# 5.net
KiCad netlist of a schematic drawn in Altium Designer
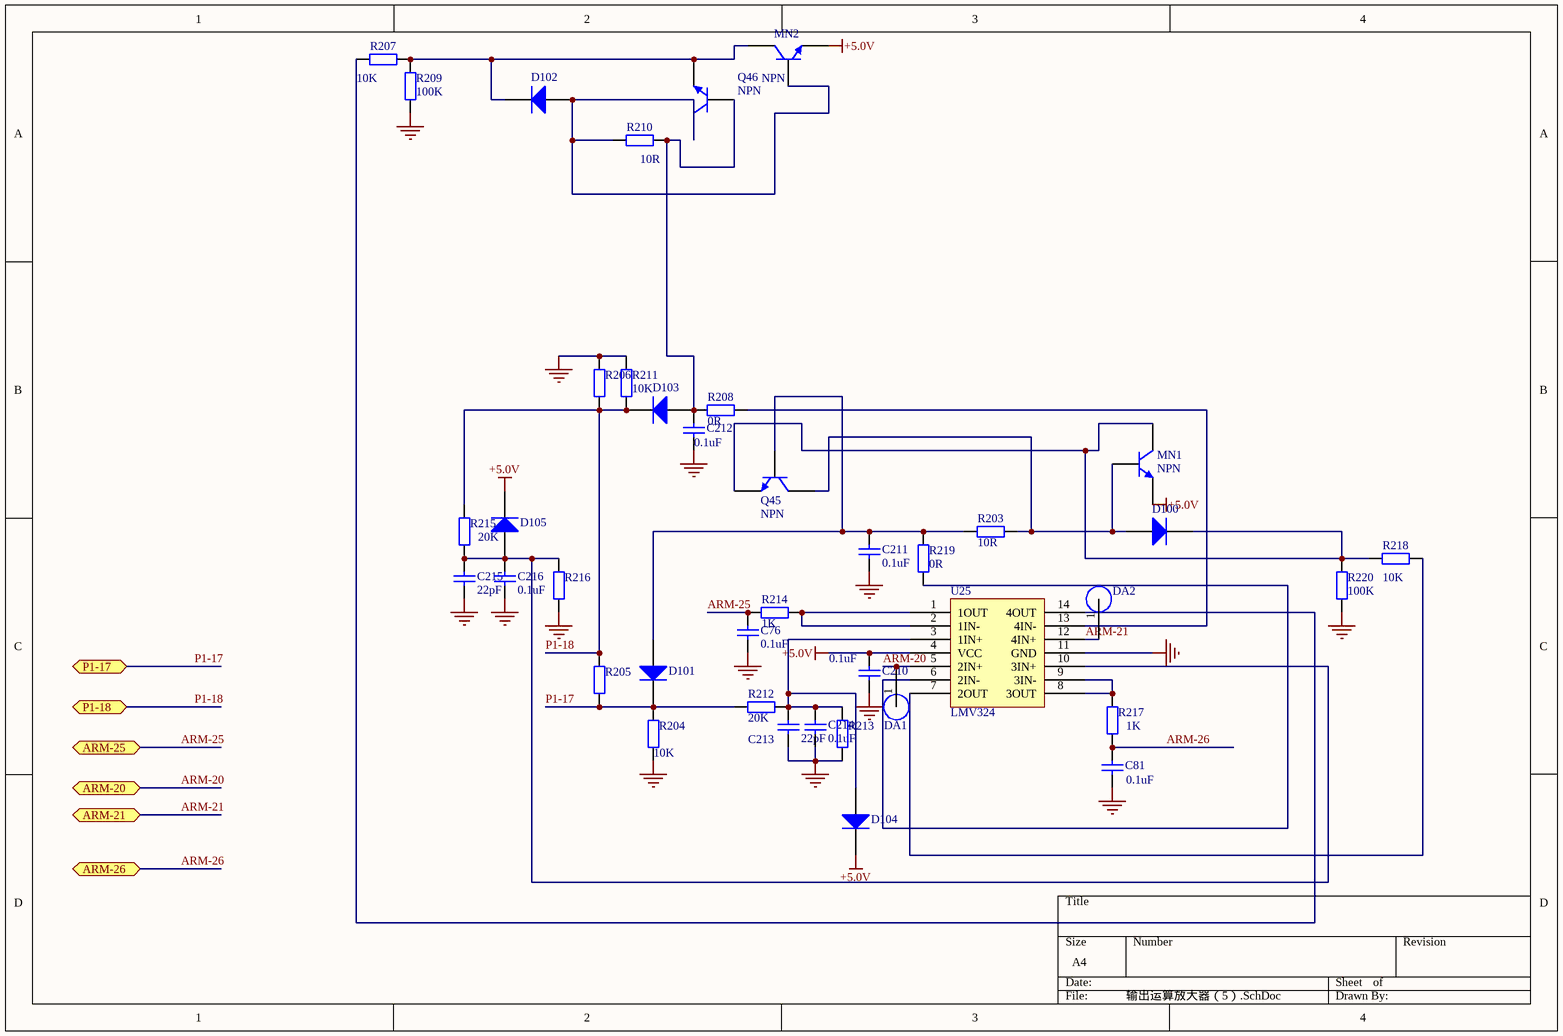
[diagram p0: 输出运算放大器（5）.SchDoc]

(export (version "E")
  (design (tool "Eeschema 10.0.6"))
  (components
    (comp (ref "C76")
      (value "0.1uF")
      (footprint "采集板3.0增加1路模拟量2:C0805")
      (description "Capacitor")
      (fields (field (name "Comment") "Cap") (field (name "PUBLISHER") "Altium Limited"))
      (libsource (lib "Miscellaneous Devices") (part "Cap"))
    )
    (comp (ref "C81")
      (value "0.1uF")
      (footprint "采集板3.0增加1路模拟量2:C0805")
      (description "Capacitor")
      (fields (field (name "Comment") "Cap") (field (name "PUBLISHER") "Altium Limited"))
      (libsource (lib "Miscellaneous Devices") (part "Cap"))
    )
    (comp (ref "C210")
      (value "0.1uF")
      (footprint "采集板3.0增加1路模拟量2:C0805")
      (description "Capacitor")
      (fields (field (name "Comment") "Cap") (field (name "PUBLISHER") "Altium Limited"))
      (libsource (lib "Miscellaneous Devices") (part "Cap"))
    )
    (comp (ref "C211")
      (value "0.1uF")
      (footprint "采集板3.0增加1路模拟量2:C0805")
      (description "Capacitor")
      (fields (field (name "Comment") "Cap") (field (name "PUBLISHER") "Altium Limited"))
      (libsource (lib "Miscellaneous Devices") (part "Cap"))
    )
    (comp (ref "C212")
      (value "0.1uF")
      (footprint "采集板3.0增加1路模拟量2:C0805")
      (description "Capacitor")
      (fields (field (name "Comment") "Cap") (field (name "PUBLISHER") "Altium Limited"))
      (libsource (lib "Miscellaneous Devices") (part "Cap"))
    )
    (comp (ref "C213")
      (value "22pF")
      (footprint "采集板3.0增加1路模拟量2:C0805")
      (description "Capacitor")
      (fields (field (name "Comment") "Cap") (field (name "PUBLISHER") "Altium Limited"))
      (libsource (lib "Miscellaneous Devices") (part "Cap"))
    )
    (comp (ref "C214")
      (value "0.1uF")
      (footprint "采集板3.0增加1路模拟量2:C0805")
      (description "Capacitor")
      (fields (field (name "Comment") "Cap") (field (name "PUBLISHER") "Altium Limited"))
      (libsource (lib "Miscellaneous Devices") (part "Cap"))
    )
    (comp (ref "C215")
      (value "22pF")
      (footprint "采集板3.0增加1路模拟量2:C0805")
      (description "Capacitor")
      (fields (field (name "Comment") "Cap") (field (name "PUBLISHER") "Altium Limited"))
      (libsource (lib "Miscellaneous Devices") (part "Cap"))
    )
    (comp (ref "C216")
      (value "0.1uF")
      (footprint "采集板3.0增加1路模拟量2:C0805")
      (description "Capacitor")
      (fields (field (name "Comment") "Cap") (field (name "PUBLISHER") "Altium Limited"))
      (libsource (lib "Miscellaneous Devices") (part "Cap"))
    )
    (comp (ref "D100")
      (value "Diode 1N4007")
      (footprint "SOD123")
      (description "1 Amp General Purpose Rectifier")
      (fields (field (name "PUBLISHER") "Altium Limited"))
      (libsource (lib "Miscellaneous Devices") (part "Diode 1N4007"))
    )
    (comp (ref "D101")
      (value "Diode 1N4007")
      (footprint "SMA")
      (description "1 Amp General Purpose Rectifier")
      (fields (field (name "PUBLISHER") "Altium Limited"))
      (libsource (lib "Miscellaneous Devices") (part "Diode 1N4007"))
    )
    (comp (ref "D102")
      (value "Diode 1N4007")
      (footprint "SOD123")
      (description "1 Amp General Purpose Rectifier")
      (fields (field (name "PUBLISHER") "Altium Limited"))
      (libsource (lib "Miscellaneous Devices") (part "Diode 1N4007"))
    )
    (comp (ref "D103")
      (value "Diode 1N4007")
      (footprint "SMA")
      (description "1 Amp General Purpose Rectifier")
      (fields (field (name "PUBLISHER") "Altium Limited"))
      (libsource (lib "Miscellaneous Devices") (part "Diode 1N4007"))
    )
    (comp (ref "D104")
      (value "Diode 1N4007")
      (footprint "SOD123")
      (description "1 Amp General Purpose Rectifier")
      (fields (field (name "PUBLISHER") "Altium Limited"))
      (libsource (lib "Miscellaneous Devices") (part "Diode 1N4007"))
    )
    (comp (ref "D105")
      (value "Diode 1N4007")
      (footprint "SOD123")
      (description "1 Amp General Purpose Rectifier")
      (fields (field (name "PUBLISHER") "Altium Limited"))
      (libsource (lib "Miscellaneous Devices") (part "Diode 1N4007"))
    )
    (comp (ref "DA1") (value "PIN") (footprint "圆形焊盘") (libsource (lib "圆孔") (part "Component_1")))
    (comp (ref "DA2") (value "PIN") (footprint "圆形焊盘") (libsource (lib "圆孔") (part "Component_1")))
    (comp (ref "MN1")
      (value "NPN")
      (footprint "SOT23-3")
      (description "NPN Bipolar Transistor")
      (fields (field (name "PUBLISHER") "Altium Limited"))
      (libsource (lib "Miscellaneous Devices") (part "NPN"))
    )
    (comp (ref "MN2")
      (value "NPN")
      (footprint "MN2")
      (description "NPN Bipolar Transistor")
      (fields (field (name "PUBLISHER") "Altium Limited"))
      (libsource (lib "Miscellaneous Devices") (part "NPN"))
    )
    (comp (ref "Q45")
      (value "NPN")
      (footprint "Q45")
      (description "NPN Bipolar Transistor")
      (fields (field (name "PUBLISHER") "Altium Limited"))
      (libsource (lib "Miscellaneous Devices") (part "NPN"))
    )
    (comp (ref "Q46")
      (value "NPN")
      (footprint "Q46")
      (description "NPN Bipolar Transistor")
      (fields (field (name "PUBLISHER") "Altium Limited"))
      (libsource (lib "Miscellaneous Devices") (part "NPN"))
    )
    (comp (ref "R203")
      (value "10R")
      (footprint "R1206")
      (description "Resistor")
      (fields (field (name "Comment") "Res2") (field (name "PUBLISHER") "Altium Limited"))
      (libsource (lib "") (part "Res2_1"))
    )
    (comp (ref "R204")
      (value "10K")
      (footprint "采集板3.0增加1路模拟量2:R0805")
      (description "Resistor")
      (fields (field (name "Comment") "Res2") (field (name "PUBLISHER") "Altium Limited"))
      (libsource (lib "") (part "Res2_3"))
    )
    (comp (ref "R205")
      (value "Res2")
      (footprint "R1206")
      (description "Resistor")
      (fields (field (name "PUBLISHER") "Altium Limited"))
      (libsource (lib "") (part "Res2_2"))
    )
    (comp (ref "R206")
      (value "Res2")
      (footprint "R1206")
      (description "Resistor")
      (fields (field (name "PUBLISHER") "Altium Limited"))
      (libsource (lib "") (part "Res2_2"))
    )
    (comp (ref "R207")
      (value "10K")
      (footprint "采集板3.0增加1路模拟量2:R0805")
      (description "Resistor")
      (fields (field (name "Comment") "Res2") (field (name "PUBLISHER") "Altium Limited"))
      (libsource (lib "") (part "Res2_1"))
    )
    (comp (ref "R208")
      (value "0R")
      (footprint "采集板3.0增加1路模拟量2:R0805")
      (description "Resistor")
      (fields (field (name "Comment") "Res2") (field (name "PUBLISHER") "Altium Limited"))
      (libsource (lib "Miscellaneous Devices") (part "Res2"))
    )
    (comp (ref "R209")
      (value "100K")
      (footprint "采集板3.0增加1路模拟量2:R0805")
      (description "Resistor")
      (fields (field (name "Comment") "Res2") (field (name "PUBLISHER") "Altium Limited"))
      (libsource (lib "") (part "Res2_3"))
    )
    (comp (ref "R210")
      (value "10R")
      (footprint "R1206")
      (description "Resistor")
      (fields (field (name "Comment") "Res2") (field (name "PUBLISHER") "Altium Limited"))
      (libsource (lib "") (part "Res2_1"))
    )
    (comp (ref "R211")
      (value "10K")
      (footprint "采集板3.0增加1路模拟量2:R0805")
      (description "Resistor")
      (fields (field (name "Comment") "Res2") (field (name "PUBLISHER") "Altium Limited"))
      (libsource (lib "") (part "Res2_2"))
    )
    (comp (ref "R212")
      (value "20K")
      (footprint "采集板3.0增加1路模拟量2:R0805")
      (description "Resistor")
      (fields (field (name "Comment") "Res2") (field (name "PUBLISHER") "Altium Limited"))
      (libsource (lib "") (part "Res2_1"))
    )
    (comp (ref "R213")
      (value "Res2")
      (footprint "R0805")
      (description "Resistor")
      (fields (field (name "PUBLISHER") "Altium Limited"))
      (libsource (lib "") (part "Res2_2"))
    )
    (comp (ref "R214")
      (value "1K")
      (footprint "采集板3.0增加1路模拟量2:R0805")
      (description "Resistor")
      (fields (field (name "Comment") "Res2") (field (name "PUBLISHER") "Altium Limited"))
      (libsource (lib "") (part "Res2_1"))
    )
    (comp (ref "R215")
      (value "20K")
      (footprint "采集板3.0增加1路模拟量2:R0805")
      (description "Resistor")
      (fields (field (name "Comment") "Res2") (field (name "PUBLISHER") "Altium Limited"))
      (libsource (lib "") (part "Res2_3"))
    )
    (comp (ref "R216")
      (value "Res2")
      (footprint "R0805")
      (description "Resistor")
      (fields (field (name "PUBLISHER") "Altium Limited"))
      (libsource (lib "") (part "Res2_2"))
    )
    (comp (ref "R217")
      (value "1K")
      (footprint "采集板3.0增加1路模拟量2:R0805")
      (description "Resistor")
      (fields (field (name "Comment") "Res2") (field (name "PUBLISHER") "Altium Limited"))
      (libsource (lib "") (part "Res2_2"))
    )
    (comp (ref "R218")
      (value "10K")
      (footprint "采集板3.0增加1路模拟量2:R0805")
      (description "Resistor")
      (fields (field (name "Comment") "Res2") (field (name "PUBLISHER") "Altium Limited"))
      (libsource (lib "Miscellaneous Devices") (part "Res2"))
    )
    (comp (ref "R219")
      (value "0R")
      (footprint "采集板3.0增加1路模拟量2:R0805")
      (description "Resistor")
      (fields (field (name "Comment") "Res2") (field (name "PUBLISHER") "Altium Limited"))
      (libsource (lib "") (part "Res2_2"))
    )
    (comp (ref "R220")
      (value "100K")
      (footprint "采集板3.0增加1路模拟量2:R0805")
      (description "Resistor")
      (fields (field (name "Comment") "Res2") (field (name "PUBLISHER") "Altium Limited"))
      (libsource (lib "") (part "Res2_2"))
    )
    (comp (ref "U25") (value "LMV324") (footprint "SOP-14") (libsource (lib "LMV324") (part "Component_1")))
  )
  (nets
    (net (code "1") (name "+5.0V") (class "Default")
      (node (ref "C210") (pin "1") (pinfunction "1_1") (pintype "passive"))
      (node (ref "D104") (pin "2") (pinfunction "K_2") (pintype "passive"))
      (node (ref "D105") (pin "2") (pinfunction "K_2") (pintype "passive"))
      (node (ref "MN1") (pin "3") (pinfunction "E_3") (pintype "passive"))
      (node (ref "MN2") (pin "3") (pinfunction "E_3") (pintype "passive"))
      (node (ref "U25") (pin "4") (pinfunction "VCC_4") (pintype "passive"))
    )
    (net (code "2") (name "/ARM-20") (class "Default")
      (node (ref "DA1") (pin "1") (pinfunction "1_1") (pintype "passive"))
      (node (ref "U25") (pin "5") (pinfunction "2IN+_5") (pintype "passive"))
    )
    (net (code "3") (name "/ARM-21") (class "Default")
      (node (ref "DA2") (pin "1") (pinfunction "1_1") (pintype "passive"))
      (node (ref "U25") (pin "12") (pinfunction "4IN+_12") (pintype "passive"))
    )
    (net (code "4") (name "/ARM-25") (class "Default")
      (node (ref "C76") (pin "2") (pinfunction "2_2") (pintype "passive"))
      (node (ref "R214") (pin "1") (pinfunction "1_1") (pintype "passive"))
    )
    (net (code "5") (name "/ARM-26") (class "Default")
      (node (ref "C81") (pin "2") (pinfunction "2_2") (pintype "passive"))
      (node (ref "R217") (pin "1") (pinfunction "1_1") (pintype "passive"))
    )
    (net (code "6") (name "/P1-17") (class "Default")
      (node (ref "D101") (pin "2") (pinfunction "K_2") (pintype "passive"))
      (node (ref "R204") (pin "1") (pinfunction "1_1") (pintype "passive"))
      (node (ref "R205") (pin "1") (pinfunction "1_1") (pintype "passive"))
      (node (ref "R212") (pin "1") (pinfunction "1_1") (pintype "passive"))
    )
    (net (code "7") (name "/P1-18") (class "Default")
      (node (ref "D103") (pin "2") (pinfunction "K_2") (pintype "passive"))
      (node (ref "R205") (pin "2") (pinfunction "2_2") (pintype "passive"))
      (node (ref "R206") (pin "1") (pinfunction "1_1") (pintype "passive"))
      (node (ref "R211") (pin "1") (pinfunction "1_1") (pintype "passive"))
      (node (ref "R215") (pin "1") (pinfunction "1_1") (pintype "passive"))
    )
    (net (code "8") (name "GND") (class "Default")
      (node (ref "C210") (pin "2") (pinfunction "2_2") (pintype "passive"))
      (node (ref "C211") (pin "2") (pinfunction "2_2") (pintype "passive"))
      (node (ref "C212") (pin "2") (pinfunction "2_2") (pintype "passive"))
      (node (ref "C213") (pin "1") (pinfunction "1_1") (pintype "passive"))
      (node (ref "C214") (pin "1") (pinfunction "1_1") (pintype "passive"))
      (node (ref "C215") (pin "1") (pinfunction "1_1") (pintype "passive"))
      (node (ref "C216") (pin "1") (pinfunction "1_1") (pintype "passive"))
      (node (ref "C76") (pin "1") (pinfunction "1_1") (pintype "passive"))
      (node (ref "C81") (pin "1") (pinfunction "1_1") (pintype "passive"))
      (node (ref "R204") (pin "2") (pinfunction "2_2") (pintype "passive"))
      (node (ref "R206") (pin "2") (pinfunction "2_2") (pintype "passive"))
      (node (ref "R209") (pin "2") (pinfunction "2_2") (pintype "passive"))
      (node (ref "R211") (pin "2") (pinfunction "2_2") (pintype "passive"))
      (node (ref "R213") (pin "1") (pinfunction "1_1") (pintype "passive"))
      (node (ref "R216") (pin "1") (pinfunction "1_1") (pintype "passive"))
      (node (ref "R220") (pin "1") (pinfunction "1_1") (pintype "passive"))
      (node (ref "U25") (pin "11") (pinfunction "GND_11") (pintype "passive"))
    )
    (net (code "9") (name "Net-(D100-A)") (class "Default")
      (node (ref "D100") (pin "1") (pinfunction "A_1") (pintype "passive"))
      (node (ref "MN1") (pin "2") (pinfunction "B_2") (pintype "passive"))
      (node (ref "Q45") (pin "1") (pinfunction "C_1") (pintype "passive"))
      (node (ref "R203") (pin "2") (pinfunction "2_2") (pintype "passive"))
    )
    (net (code "10") (name "Net-(D100-K)") (class "Default")
      (node (ref "D100") (pin "2") (pinfunction "K_2") (pintype "passive"))
      (node (ref "MN1") (pin "1") (pinfunction "C_1") (pintype "passive"))
      (node (ref "Q45") (pin "3") (pinfunction "E_3") (pintype "passive"))
      (node (ref "R218") (pin "2") (pinfunction "2_2") (pintype "passive"))
      (node (ref "R220") (pin "2") (pinfunction "2_2") (pintype "passive"))
    )
    (net (code "11") (name "Net-(D101-A)") (class "Default")
      (node (ref "C211") (pin "1") (pinfunction "1_1") (pintype "passive"))
      (node (ref "D101") (pin "1") (pinfunction "A_1") (pintype "passive"))
      (node (ref "Q45") (pin "2") (pinfunction "B_2") (pintype "passive"))
      (node (ref "R203") (pin "1") (pinfunction "1_1") (pintype "passive"))
      (node (ref "R219") (pin "2") (pinfunction "2_2") (pintype "passive"))
    )
    (net (code "12") (name "Net-(D102-A)") (class "Default")
      (node (ref "D102") (pin "1") (pinfunction "A_1") (pintype "passive"))
      (node (ref "MN2") (pin "2") (pinfunction "B_2") (pintype "passive"))
      (node (ref "Q46") (pin "1") (pinfunction "C_1") (pintype "passive"))
      (node (ref "R210") (pin "1") (pinfunction "1_1") (pintype "passive"))
    )
    (net (code "13") (name "Net-(D102-K)") (class "Default")
      (node (ref "D102") (pin "2") (pinfunction "K_2") (pintype "passive"))
      (node (ref "MN2") (pin "1") (pinfunction "C_1") (pintype "passive"))
      (node (ref "Q46") (pin "3") (pinfunction "E_3") (pintype "passive"))
      (node (ref "R207") (pin "2") (pinfunction "2_2") (pintype "passive"))
      (node (ref "R209") (pin "1") (pinfunction "1_1") (pintype "passive"))
    )
    (net (code "14") (name "Net-(D103-A)") (class "Default")
      (node (ref "C212") (pin "1") (pinfunction "1_1") (pintype "passive"))
      (node (ref "D103") (pin "1") (pinfunction "A_1") (pintype "passive"))
      (node (ref "Q46") (pin "2") (pinfunction "B_2") (pintype "passive"))
      (node (ref "R208") (pin "2") (pinfunction "2_2") (pintype "passive"))
      (node (ref "R210") (pin "2") (pinfunction "2_2") (pintype "passive"))
    )
    (net (code "15") (name "Net-(D104-A)") (class "Default")
      (node (ref "C213") (pin "2") (pinfunction "2_2") (pintype "passive"))
      (node (ref "C214") (pin "2") (pinfunction "2_2") (pintype "passive"))
      (node (ref "D104") (pin "1") (pinfunction "A_1") (pintype "passive"))
      (node (ref "R212") (pin "2") (pinfunction "2_2") (pintype "passive"))
      (node (ref "R213") (pin "2") (pinfunction "2_2") (pintype "passive"))
      (node (ref "U25") (pin "3") (pinfunction "1IN+_3") (pintype "passive"))
    )
    (net (code "16") (name "Net-(D105-A)") (class "Default")
      (node (ref "C215") (pin "2") (pinfunction "2_2") (pintype "passive"))
      (node (ref "C216") (pin "2") (pinfunction "2_2") (pintype "passive"))
      (node (ref "D105") (pin "1") (pinfunction "A_1") (pintype "passive"))
      (node (ref "R215") (pin "2") (pinfunction "2_2") (pintype "passive"))
      (node (ref "R216") (pin "2") (pinfunction "2_2") (pintype "passive"))
      (node (ref "U25") (pin "10") (pinfunction "3IN+_10") (pintype "passive"))
    )
    (net (code "17") (name "Net-(U25-1IN-)") (class "Default")
      (node (ref "R214") (pin "2") (pinfunction "2_2") (pintype "passive"))
      (node (ref "U25") (pin "1") (pinfunction "1OUT_1") (pintype "passive"))
      (node (ref "U25") (pin "2") (pinfunction "1IN-_2") (pintype "passive"))
    )
    (net (code "18") (name "Net-(U25-2IN-)") (class "Default")
      (node (ref "R219") (pin "1") (pinfunction "1_1") (pintype "passive"))
      (node (ref "U25") (pin "6") (pinfunction "2IN-_6") (pintype "passive"))
    )
    (net (code "19") (name "Net-(U25-2OUT)") (class "Default")
      (node (ref "R218") (pin "1") (pinfunction "1_1") (pintype "passive"))
      (node (ref "U25") (pin "7") (pinfunction "2OUT_7") (pintype "passive"))
    )
    (net (code "20") (name "Net-(U25-3IN-)") (class "Default")
      (node (ref "R217") (pin "2") (pinfunction "2_2") (pintype "passive"))
      (node (ref "U25") (pin "8") (pinfunction "3OUT_8") (pintype "passive"))
      (node (ref "U25") (pin "9") (pinfunction "3IN-_9") (pintype "passive"))
    )
    (net (code "21") (name "Net-(U25-4IN-)") (class "Default")
      (node (ref "R208") (pin "1") (pinfunction "1_1") (pintype "passive"))
      (node (ref "U25") (pin "13") (pinfunction "4IN-_13") (pintype "passive"))
    )
    (net (code "22") (name "Net-(U25-4OUT)") (class "Default")
      (node (ref "R207") (pin "1") (pinfunction "1_1") (pintype "passive"))
      (node (ref "U25") (pin "14") (pinfunction "4OUT_14") (pintype "passive"))
    )
  )
)
